# Target.net
KiCad netlist of a schematic drawn in Altium Designer
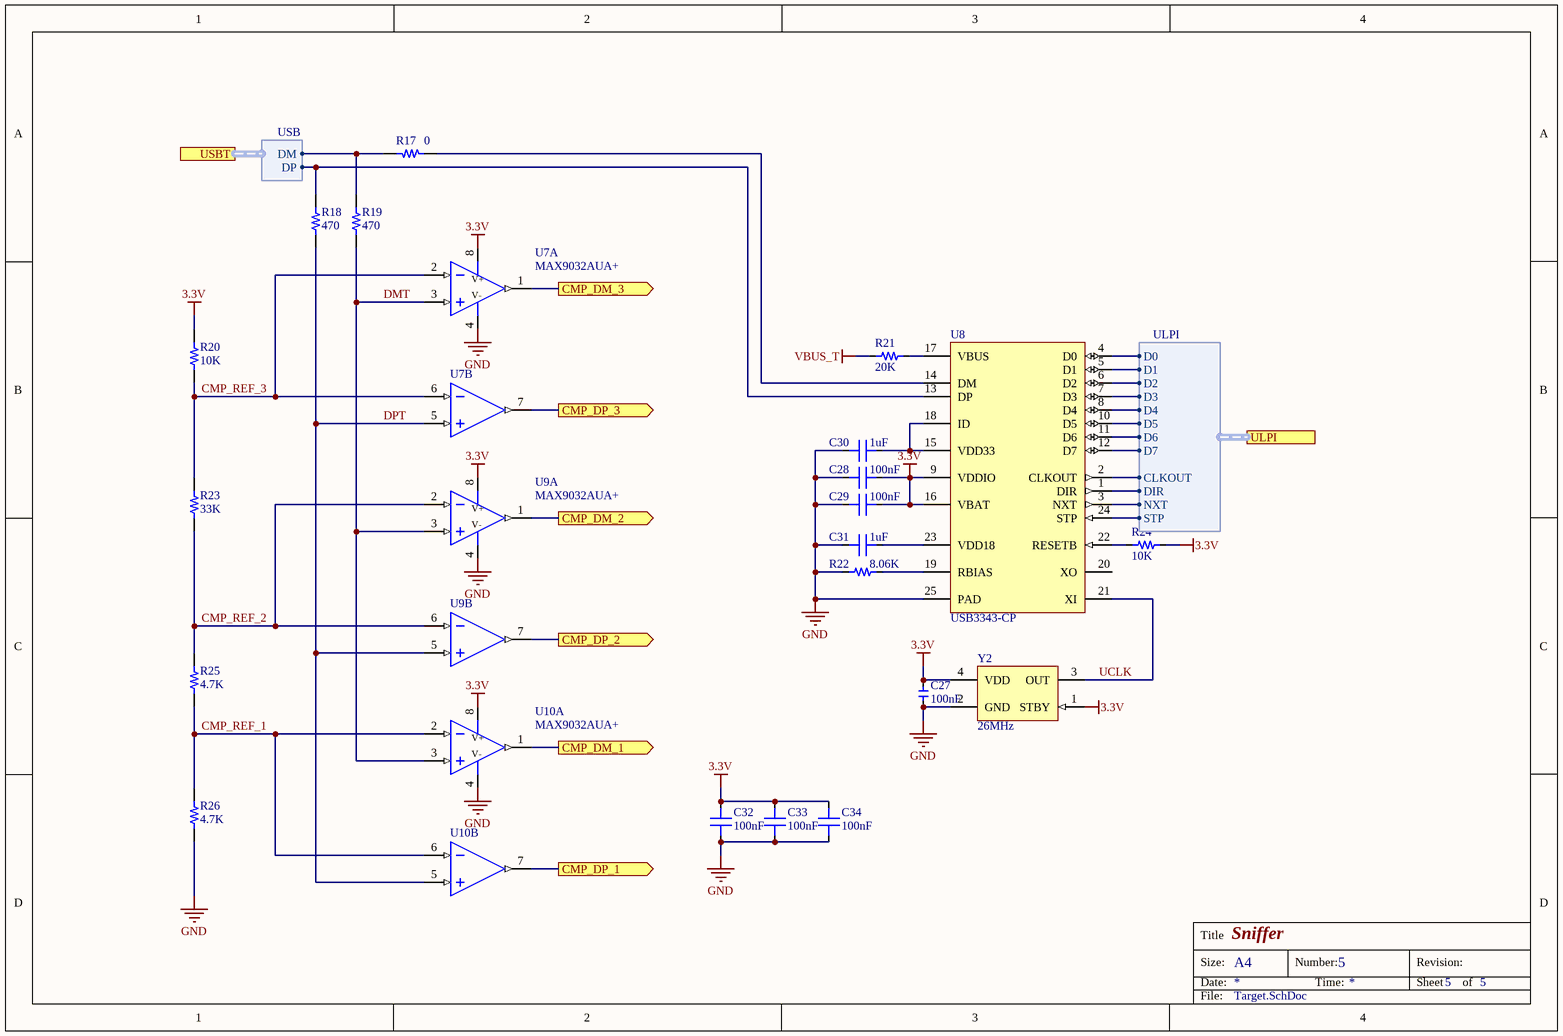
[diagram p0: Target.SchDoc]

(export (version "E")
  (design (tool "Eeschema 10.0.6"))
  (components
    (comp (ref "C27")
      (value "100nF")
      (footprint "CAP 0402/1005")
      (description "CAP CER 100NF 25V X5R 0402")
      (fields (field (name "PART NUMBER") "GRM155R61E104KA87D") (field (name "MANUFACTURER") "Murata"))
      (libsource (lib "") (part "Capacitor_1"))
    )
    (comp (ref "C28")
      (value "100nF")
      (footprint "CAP 0402/1005")
      (description "CAP CER 100NF 25V X5R 0402")
      (fields (field (name "PART NUMBER") "GRM155R61E104KA87D") (field (name "MANUFACTURER") "Murata"))
      (libsource (lib "Mengsklib") (part "Capacitor"))
    )
    (comp (ref "C29")
      (value "100nF")
      (footprint "CAP 0402/1005")
      (description "CAP CER 100NF 25V X5R 0402")
      (fields (field (name "PART NUMBER") "GRM155R61E104KA87D") (field (name "MANUFACTURER") "Murata"))
      (libsource (lib "Mengsklib") (part "Capacitor"))
    )
    (comp (ref "C30")
      (value "1uF")
      (footprint "CAP 0402/1005")
      (description "CAP CER 1UF 6.3V X5R 0402")
      (fields (field (name "PART NUMBER") "GRM155R60J105KE19D") (field (name "MANUFACTURER") "Murata"))
      (libsource (lib "Mengsklib") (part "Capacitor"))
    )
    (comp (ref "C31")
      (value "1uF")
      (footprint "CAP 0402/1005")
      (description "CAP CER 1UF 6.3V X5R 0402")
      (fields (field (name "PART NUMBER") "GRM155R60J105KE19D") (field (name "MANUFACTURER") "Murata"))
      (libsource (lib "Mengsklib") (part "Capacitor"))
    )
    (comp (ref "C32")
      (value "100nF")
      (footprint "CAP 0402/1005")
      (description "CAP CER 100NF 25V X5R 0402")
      (fields (field (name "PART NUMBER") "GRM155R61E104KA87D") (field (name "MANUFACTURER") "Murata"))
      (libsource (lib "Mengsklib") (part "Capacitor"))
    )
    (comp (ref "C33")
      (value "100nF")
      (footprint "CAP 0402/1005")
      (description "CAP CER 100NF 25V X5R 0402")
      (fields (field (name "PART NUMBER") "GRM155R61E104KA87D") (field (name "MANUFACTURER") "Murata"))
      (libsource (lib "Mengsklib") (part "Capacitor"))
    )
    (comp (ref "C34")
      (value "100nF")
      (footprint "CAP 0402/1005")
      (description "CAP CER 100NF 25V X5R 0402")
      (fields (field (name "PART NUMBER") "GRM155R61E104KA87D") (field (name "MANUFACTURER") "Murata"))
      (libsource (lib "Mengsklib") (part "Capacitor"))
    )
    (comp (ref "R17")
      (value "0")
      (footprint "RES 0402/1005")
      (description "RES SMD 0 OHM 5% 1/16W 0402")
      (fields (field (name "PART NUMBER") "RC0402JR-070RL") (field (name "MANUFACTURER") "Yageo"))
      (libsource (lib "Mengsklib") (part "Resistor"))
    )
    (comp (ref "R18")
      (value "470")
      (footprint "RES 0402/1005")
      (description "RES SMD 470 OHM 1% 1/16W 0402")
      (fields (field (name "PART NUMBER") "RC0402FR-07470RL") (field (name "MANUFACTURER") "Yageo"))
      (libsource (lib "Mengsklib") (part "Resistor"))
    )
    (comp (ref "R19")
      (value "470")
      (footprint "RES 0402/1005")
      (description "RES SMD 470 OHM 1% 1/16W 0402")
      (fields (field (name "PART NUMBER") "RC0402FR-07470RL") (field (name "MANUFACTURER") "Yageo"))
      (libsource (lib "Mengsklib") (part "Resistor"))
    )
    (comp (ref "R20")
      (value "10K")
      (footprint "RES 0402/1005")
      (description "RES SMD 10K OHM 1% 1/16W 0402")
      (fields (field (name "PART NUMBER") "RC0402FR-0710KL") (field (name "MANUFACTURER") "Yageo"))
      (libsource (lib "Mengsklib") (part "Resistor"))
    )
    (comp (ref "R21")
      (value "20K")
      (footprint "RES 0402/1005")
      (description "RES SMD 20K OHM 1% 1/16W 0402")
      (fields (field (name "PART NUMBER") "RC0402FR-0720KL") (field (name "MANUFACTURER") "Yageo"))
      (libsource (lib "") (part "Resistor_1"))
    )
    (comp (ref "R22")
      (value "8.06K")
      (footprint "RES 0402/1005")
      (description "RES SMD 8.06K OHM 1% 1/16W 0402")
      (fields (field (name "PART NUMBER") "RC0402FR-078K06L") (field (name "MANUFACTURER") "Yageo"))
      (libsource (lib "") (part "Resistor_1"))
    )
    (comp (ref "R23")
      (value "33K")
      (footprint "RES 0402/1005")
      (description "RES SMD 33K OHM 1% 1/16W 0402")
      (fields (field (name "PART NUMBER") "RC0402FR-0733KL") (field (name "MANUFACTURER") "Yageo"))
      (libsource (lib "Mengsklib") (part "Resistor"))
    )
    (comp (ref "R24")
      (value "10K")
      (footprint "RES 0402/1005")
      (description "RES SMD 10K OHM 1% 1/16W 0402")
      (fields (field (name "PART NUMBER") "RC0402FR-0710KL") (field (name "MANUFACTURER") "Yageo"))
      (libsource (lib "") (part "Resistor_1"))
    )
    (comp (ref "R25")
      (value "4.7K")
      (footprint "RES 0402/1005")
      (description "RES SMD 4.7K OHM 1% 1/16W 0402")
      (fields (field (name "PART NUMBER") "RC0402FR-074K7L") (field (name "MANUFACTURER") "Yageo"))
      (libsource (lib "Mengsklib") (part "Resistor"))
    )
    (comp (ref "R26")
      (value "4.7K")
      (footprint "RES 0402/1005")
      (description "RES SMD 4.7K OHM 1% 1/16W 0402")
      (fields (field (name "PART NUMBER") "RC0402FR-074K7L") (field (name "MANUFACTURER") "Yageo"))
      (libsource (lib "Mengsklib") (part "Resistor"))
    )
    (comp (ref "U7")
      (value "MAX9032AUA+")
      (footprint "TSOP65P490X110-8N")
      (description "IC COMP PP TSSOP-8")
      (fields (field (name "MANUFACTURER") "AD"))
      (libsource (lib "Mengsklib") (part "COMP_2CH_PP"))
    )
    (comp (ref "U8")
      (value "USB3343-CP")
      (footprint "QFN50P400X400X80_HS-25N")
      (description "USB ULPI PHY 24QFN")
      (fields (field (name "MANUFACTURER") "Microchip"))
      (libsource (lib "Mengsklib") (part "USB3343"))
    )
    (comp (ref "U9")
      (value "MAX9032AUA+")
      (footprint "TSOP65P490X110-8N")
      (description "IC COMP PP TSSOP-8")
      (fields (field (name "MANUFACTURER") "AD"))
      (libsource (lib "Mengsklib") (part "COMP_2CH_PP"))
    )
    (comp (ref "U10")
      (value "MAX9032AUA+")
      (footprint "TSOP65P490X110-8N")
      (description "IC COMP PP TSSOP-8")
      (fields (field (name "MANUFACTURER") "AD"))
      (libsource (lib "Mengsklib") (part "COMP_2CH_PP"))
    )
    (comp (ref "Y2")
      (value "26MHz")
      (footprint "WE-SPXO_IQXO-540")
      (description "OSC XO 26MHz 3.3V 2016 SMD")
      (fields (field (name "PART NUMBER") "831056245") (field (name "MANUFACTURER") "Wurth"))
      (libsource (lib "Mengsklib") (part "WE-SPXO_IQXO-540"))
    )
  )
  (nets
    (net (code "3") (name "/CLKOUT") (class "Default")
      (node (ref "U8") (pin "2") (pinfunction "CLKOUT_2") (pintype "output"))
    )
    (net (code "4") (name "/CMP_DM_1") (class "Default")
      (node (ref "U10") (pin "1") (pinfunction "OUTA_1") (pintype "output"))
    )
    (net (code "5") (name "/CMP_DM_2") (class "Default")
      (node (ref "U9") (pin "1") (pinfunction "OUTA_1") (pintype "output"))
    )
    (net (code "6") (name "/CMP_DM_3") (class "Default")
      (node (ref "U7") (pin "1") (pinfunction "OUTA_1") (pintype "output"))
    )
    (net (code "7") (name "/CMP_DP_1") (class "Default")
      (node (ref "U10") (pin "7") (pinfunction "OUTB_7") (pintype "output"))
    )
    (net (code "8") (name "/CMP_DP_2") (class "Default")
      (node (ref "U9") (pin "7") (pinfunction "OUTB_7") (pintype "output"))
    )
    (net (code "9") (name "/CMP_DP_3") (class "Default")
      (node (ref "U7") (pin "7") (pinfunction "OUTB_7") (pintype "output"))
    )
    (net (code "10") (name "/CMP_REF_1") (class "Default")
      (node (ref "R25") (pin "1") (pinfunction "1_1") (pintype "passive"))
      (node (ref "R26") (pin "2") (pinfunction "2_2") (pintype "passive"))
      (node (ref "U10") (pin "2") (pinfunction "-INA_2") (pintype "input"))
      (node (ref "U10") (pin "6") (pinfunction "-INB_6") (pintype "input"))
    )
    (net (code "11") (name "/CMP_REF_2") (class "Default")
      (node (ref "R23") (pin "1") (pinfunction "1_1") (pintype "passive"))
      (node (ref "R25") (pin "2") (pinfunction "2_2") (pintype "passive"))
      (node (ref "U9") (pin "2") (pinfunction "-INA_2") (pintype "input"))
      (node (ref "U9") (pin "6") (pinfunction "-INB_6") (pintype "input"))
    )
    (net (code "12") (name "/CMP_REF_3") (class "Default")
      (node (ref "R20") (pin "1") (pinfunction "1_1") (pintype "passive"))
      (node (ref "R23") (pin "2") (pinfunction "2_2") (pintype "passive"))
      (node (ref "U7") (pin "2") (pinfunction "-INA_2") (pintype "input"))
      (node (ref "U7") (pin "6") (pinfunction "-INB_6") (pintype "input"))
    )
    (net (code "13") (name "/D0") (class "Default")
      (node (ref "U8") (pin "4") (pinfunction "D0_4") (pintype "bidirectional"))
    )
    (net (code "14") (name "/D1") (class "Default")
      (node (ref "U8") (pin "5") (pinfunction "D1_5") (pintype "bidirectional"))
    )
    (net (code "15") (name "/D2") (class "Default")
      (node (ref "U8") (pin "6") (pinfunction "D2_6") (pintype "bidirectional"))
    )
    (net (code "16") (name "/D3") (class "Default")
      (node (ref "U8") (pin "7") (pinfunction "D3_7") (pintype "bidirectional"))
    )
    (net (code "17") (name "/D4") (class "Default")
      (node (ref "U8") (pin "8") (pinfunction "D4_8") (pintype "bidirectional"))
    )
    (net (code "18") (name "/D5") (class "Default")
      (node (ref "U8") (pin "10") (pinfunction "D5_10") (pintype "bidirectional"))
    )
    (net (code "19") (name "/D6") (class "Default")
      (node (ref "U8") (pin "11") (pinfunction "D6_11") (pintype "bidirectional"))
    )
    (net (code "20") (name "/D7") (class "Default")
      (node (ref "U8") (pin "12") (pinfunction "D7_12") (pintype "bidirectional"))
    )
    (net (code "21") (name "/DIR") (class "Default")
      (node (ref "U8") (pin "1") (pinfunction "DIR_1") (pintype "output"))
    )
    (net (code "22") (name "/DM") (class "Default")
      (node (ref "R17") (pin "2") (pinfunction "2_2") (pintype "passive"))
      (node (ref "R19") (pin "2") (pinfunction "2_2") (pintype "passive"))
    )
    (net (code "23") (name "/DMT") (class "Default")
      (node (ref "R19") (pin "1") (pinfunction "1_1") (pintype "passive"))
      (node (ref "U10") (pin "3") (pinfunction "+INA_3") (pintype "input"))
      (node (ref "U7") (pin "3") (pinfunction "+INA_3") (pintype "input"))
      (node (ref "U9") (pin "3") (pinfunction "+INA_3") (pintype "input"))
    )
    (net (code "24") (name "/DP") (class "Default")
      (node (ref "R18") (pin "2") (pinfunction "2_2") (pintype "passive"))
      (node (ref "U8") (pin "13") (pinfunction "DP_13") (pintype "passive"))
    )
    (net (code "25") (name "/DPT") (class "Default")
      (node (ref "R18") (pin "1") (pinfunction "1_1") (pintype "passive"))
      (node (ref "U10") (pin "5") (pinfunction "+INB_5") (pintype "input"))
      (node (ref "U7") (pin "5") (pinfunction "+INB_5") (pintype "input"))
      (node (ref "U9") (pin "5") (pinfunction "+INB_5") (pintype "input"))
    )
    (net (code "26") (name "/NXT") (class "Default")
      (node (ref "U8") (pin "3") (pinfunction "NXT_3") (pintype "output"))
    )
    (net (code "27") (name "/STP") (class "Default")
      (node (ref "U8") (pin "24") (pinfunction "STP_24") (pintype "input"))
    )
    (net (code "28") (name "/UCLK") (class "Default")
      (node (ref "U8") (pin "21") (pinfunction "XI_21") (pintype "passive"))
      (node (ref "Y2") (pin "3") (pinfunction "OUT_3") (pintype "passive"))
    )
    (net (code "31") (name "3.3V") (class "Default")
      (node (ref "C27") (pin "1") (pinfunction "1_1") (pintype "passive"))
      (node (ref "C28") (pin "1") (pinfunction "1_1") (pintype "passive"))
      (node (ref "C29") (pin "2") (pinfunction "2_2") (pintype "passive"))
      (node (ref "C32") (pin "1") (pinfunction "1_1") (pintype "passive"))
      (node (ref "C33") (pin "1") (pinfunction "1_1") (pintype "passive"))
      (node (ref "C34") (pin "1") (pinfunction "1_1") (pintype "passive"))
      (node (ref "R20") (pin "2") (pinfunction "2_2") (pintype "passive"))
      (node (ref "R24") (pin "1") (pinfunction "1_1") (pintype "passive"))
      (node (ref "U10") (pin "8") (pinfunction "V+_8") (pintype "power_in"))
      (node (ref "U7") (pin "8") (pinfunction "V+_8") (pintype "power_in"))
      (node (ref "U8") (pin "16") (pinfunction "VBAT_16") (pintype "passive"))
      (node (ref "U8") (pin "9") (pinfunction "VDDIO_9") (pintype "passive"))
      (node (ref "U9") (pin "8") (pinfunction "V+_8") (pintype "power_in"))
      (node (ref "Y2") (pin "1") (pinfunction "STBY_1") (pintype "input"))
      (node (ref "Y2") (pin "4") (pinfunction "VDD_4") (pintype "passive"))
    )
    (net (code "32") (name "GND") (class "Default")
      (node (ref "C27") (pin "2") (pinfunction "2_2") (pintype "passive"))
      (node (ref "C28") (pin "2") (pinfunction "2_2") (pintype "passive"))
      (node (ref "C29") (pin "1") (pinfunction "1_1") (pintype "passive"))
      (node (ref "C30") (pin "1") (pinfunction "1_1") (pintype "passive"))
      (node (ref "C31") (pin "1") (pinfunction "1_1") (pintype "passive"))
      (node (ref "C32") (pin "2") (pinfunction "2_2") (pintype "passive"))
      (node (ref "C33") (pin "2") (pinfunction "2_2") (pintype "passive"))
      (node (ref "C34") (pin "2") (pinfunction "2_2") (pintype "passive"))
      (node (ref "R22") (pin "1") (pinfunction "1_1") (pintype "passive"))
      (node (ref "R26") (pin "1") (pinfunction "1_1") (pintype "passive"))
      (node (ref "U10") (pin "4") (pinfunction "V-_4") (pintype "power_in"))
      (node (ref "U7") (pin "4") (pinfunction "V-_4") (pintype "power_in"))
      (node (ref "U8") (pin "25") (pinfunction "PAD_25") (pintype "passive"))
      (node (ref "U9") (pin "4") (pinfunction "V-_4") (pintype "power_in"))
      (node (ref "Y2") (pin "2") (pinfunction "GND_2") (pintype "passive"))
    )
    (net (code "33") (name "Net-(U8-DM)") (class "Default")
      (node (ref "R17") (pin "1") (pinfunction "1_1") (pintype "passive"))
      (node (ref "U8") (pin "14") (pinfunction "DM_14") (pintype "passive"))
    )
    (net (code "34") (name "Net-(U8-ID)") (class "Default")
      (node (ref "C30") (pin "2") (pinfunction "2_2") (pintype "passive"))
      (node (ref "U8") (pin "15") (pinfunction "VDD33_15") (pintype "passive"))
      (node (ref "U8") (pin "18") (pinfunction "ID_18") (pintype "passive"))
    )
    (net (code "35") (name "Net-(U8-RBIAS)") (class "Default")
      (node (ref "R22") (pin "2") (pinfunction "2_2") (pintype "passive"))
      (node (ref "U8") (pin "19") (pinfunction "RBIAS_19") (pintype "passive"))
    )
    (net (code "36") (name "Net-(U8-RESETB)") (class "Default")
      (node (ref "R24") (pin "2") (pinfunction "2_2") (pintype "passive"))
      (node (ref "U8") (pin "22") (pinfunction "RESETB_22") (pintype "input"))
    )
    (net (code "37") (name "Net-(U8-VBUS)") (class "Default")
      (node (ref "R21") (pin "2") (pinfunction "2_2") (pintype "passive"))
      (node (ref "U8") (pin "17") (pinfunction "VBUS_17") (pintype "passive"))
    )
    (net (code "38") (name "Net-(U8-VDD18)") (class "Default")
      (node (ref "C31") (pin "2") (pinfunction "2_2") (pintype "passive"))
      (node (ref "U8") (pin "23") (pinfunction "VDD18_23") (pintype "passive"))
    )
    (net (code "39") (name "VBUS_T") (class "Default")
      (node (ref "R21") (pin "1") (pinfunction "1_1") (pintype "passive"))
    )
    (net (code "40") (name "unconnected-(U8-XO-Pad20)") (class "Default")
      (node (ref "U8") (pin "20") (pinfunction "XO_20") (pintype "passive"))
    )
  )
)
